# Qwiic_Fuel_Gauge_-_MAX17048.net
KiCad netlist of a schematic drawn in EAGLE
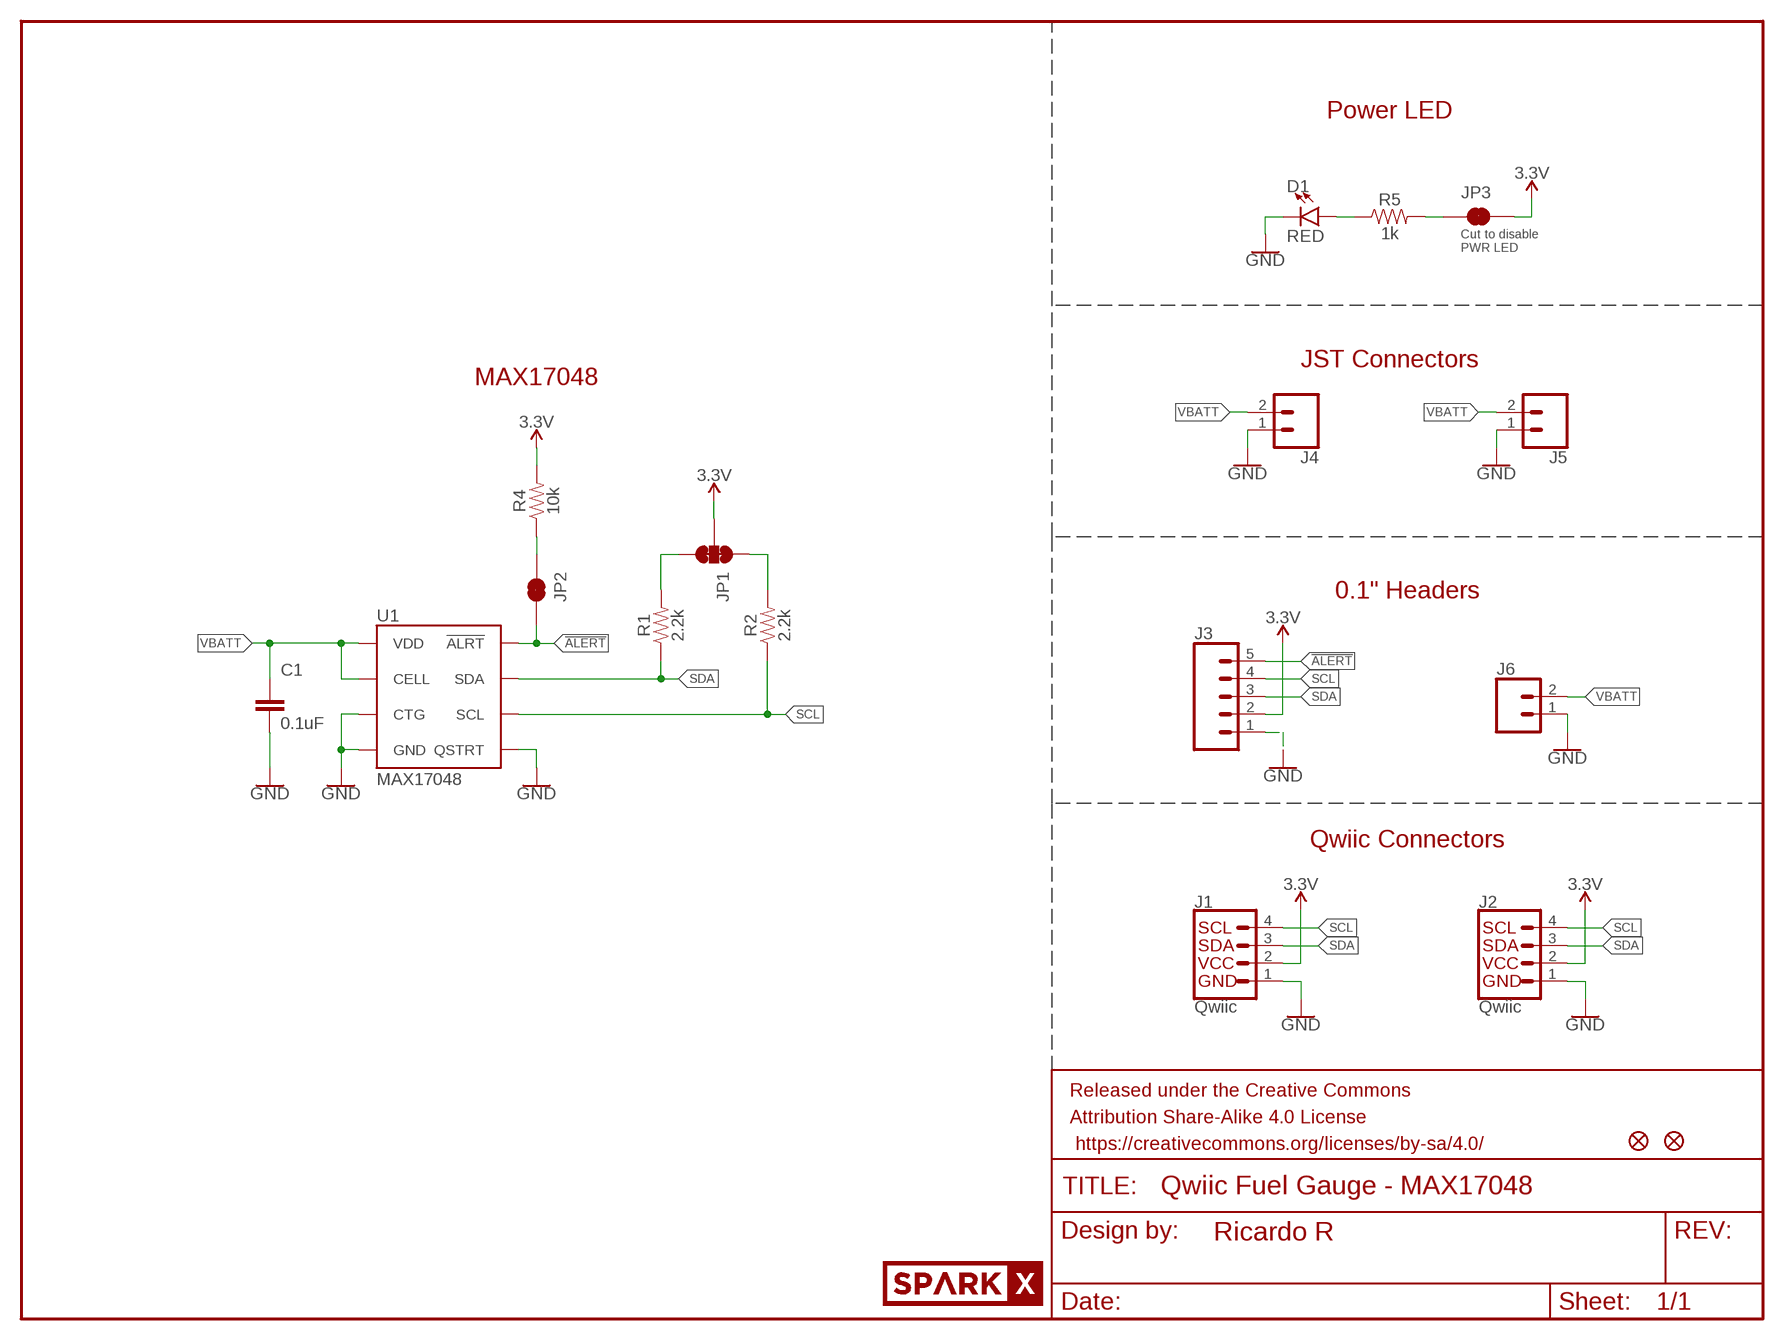
[diagram p0: schematic, sheet 1]

(export (version "E")
  (design (tool "Eeschema 10.0.6"))
  (components
    (comp (ref "C1")
      (value "0.1uF")
      (footprint "eagle-import:0603")
      (libsource (lib "eagle-import") (part "0.1UF-0603-25V-(+80/-20%)"))
    )
    (comp (ref "D1")
      (value "RED")
      (footprint "eagle-import:LED-0603")
      (libsource (lib "eagle-import") (part "LED-RED0603"))
    )
    (comp (ref "FD1")
      (value "FIDUCIAL1X2")
      (footprint "eagle-import:FIDUCIAL-1X2")
      (libsource (lib "eagle-import") (part "FIDUCIAL1X2"))
    )
    (comp (ref "FD2")
      (value "FIDUCIAL1X2")
      (footprint "eagle-import:FIDUCIAL-1X2")
      (libsource (lib "eagle-import") (part "FIDUCIAL1X2"))
    )
    (comp (ref "FRAME1")
      (value "FRAME-LETTERNO_PACKAGE")
      (footprint "eagle-import:DUMMY")
      (fields (field (name "DESIGNER") "Ricardo R") (field (name "DESIGNER_1") "Ricardo R"))
      (libsource (lib "eagle-import") (part "FRAME-LETTERNO_PACKAGE"))
    )
    (comp (ref "J1")
      (value "Qwiic")
      (footprint "eagle-import:JST04_1MM_RA")
      (libsource (lib "eagle-import") (part "QWIIC_CONNECTORJS-1MM"))
    )
    (comp (ref "J2")
      (value "Qwiic")
      (footprint "eagle-import:JST04_1MM_RA")
      (libsource (lib "eagle-import") (part "QWIIC_CONNECTORJS-1MM"))
    )
    (comp (ref "J3")
      (value "CONN_05NO_SILK")
      (footprint "eagle-import:1X05_NO_SILK")
      (libsource (lib "eagle-import") (part "CONN_05NO_SILK"))
    )
    (comp (ref "J4")
      (value "CONN_02-JST-2MM-SMT")
      (footprint "eagle-import:JST-2-SMD")
      (libsource (lib "eagle-import") (part "CONN_02-JST-2MM-SMT"))
    )
    (comp (ref "J5")
      (value "CONN_02-JST-2MM-SMT")
      (footprint "eagle-import:JST-2-SMD")
      (libsource (lib "eagle-import") (part "CONN_02-JST-2MM-SMT"))
    )
    (comp (ref "J6")
      (value "CONN_021X02_NO_SILK")
      (footprint "eagle-import:1X02_NO_SILK")
      (libsource (lib "eagle-import") (part "CONN_021X02_NO_SILK"))
    )
    (comp (ref "JP1")
      (value "JUMPER-SMT_3_2-NC_TRACE_SILK")
      (footprint "eagle-import:SMT-JUMPER_3_2-NC_TRACE_SILK")
      (libsource (lib "eagle-import") (part "JUMPER-SMT_3_2-NC_TRACE_SILK"))
    )
    (comp (ref "JP2")
      (value "JUMPER-SMT_2_NC_TRACE_SILK")
      (footprint "eagle-import:SMT-JUMPER_2_NC_TRACE_SILK")
      (libsource (lib "eagle-import") (part "JUMPER-SMT_2_NC_TRACE_SILK"))
    )
    (comp (ref "JP3")
      (value "JUMPER-SMT_2_NC_TRACE_SILK")
      (footprint "eagle-import:SMT-JUMPER_2_NC_TRACE_SILK")
      (libsource (lib "eagle-import") (part "JUMPER-SMT_2_NC_TRACE_SILK"))
    )
    (comp (ref "R1")
      (value "2.2k")
      (footprint "eagle-import:0603")
      (libsource (lib "eagle-import") (part "2.2KOHM-0603-1/10W-1%"))
    )
    (comp (ref "R2")
      (value "2.2k")
      (footprint "eagle-import:0603")
      (libsource (lib "eagle-import") (part "2.2KOHM-0603-1/10W-1%"))
    )
    (comp (ref "R4")
      (value "10k")
      (footprint "eagle-import:0603")
      (libsource (lib "eagle-import") (part "10KOHM-0603-1/10W-1%"))
    )
    (comp (ref "R5")
      (value "1k")
      (footprint "eagle-import:0603")
      (libsource (lib "eagle-import") (part "1KOHM-0603-1/10W-1%"))
    )
    (comp (ref "U$30")
      (value "SPARKX-LOGO4")
      (footprint "eagle-import:SPARKX-MEDIUM")
      (libsource (lib "eagle-import") (part "SPARKX-LOGO4"))
    )
    (comp (ref "U1")
      (value "MAX17048")
      (footprint "eagle-import:DFN-8")
      (libsource (lib "eagle-import") (part "MAX17048DFN8"))
    )
  )
  (nets
    (net (code "1") (name "/~{ALERT}") (class "Default")
      (node (ref "J3") (pin "5") (pinfunction "5_5") (pintype "passive"))
      (node (ref "JP2") (pin "2") (pinfunction "2_2") (pintype "passive"))
      (node (ref "U1") (pin "5") (pinfunction "~{ALRT}_5") (pintype "bidirectional"))
    )
    (net (code "2") (name "3.3V") (class "Default")
      (node (ref "J1") (pin "2") (pinfunction "2_2") (pintype "power_in"))
      (node (ref "J2") (pin "2") (pinfunction "2_2") (pintype "power_in"))
      (node (ref "J3") (pin "2") (pinfunction "2_2") (pintype "passive"))
      (node (ref "JP1") (pin "2") (pinfunction "2_2") (pintype "passive"))
      (node (ref "JP3") (pin "2") (pinfunction "2_2") (pintype "passive"))
      (node (ref "R4") (pin "2") (pinfunction "2_2") (pintype "passive"))
    )
    (net (code "3") (name "GND") (class "Default")
      (node (ref "C1") (pin "2") (pinfunction "2_2") (pintype "passive"))
      (node (ref "D1") (pin "C") (pinfunction "C_C") (pintype "passive"))
      (node (ref "J1") (pin "1") (pinfunction "1_1") (pintype "power_in"))
      (node (ref "J2") (pin "1") (pinfunction "1_1") (pintype "power_in"))
      (node (ref "J3") (pin "1") (pinfunction "1_1") (pintype "passive"))
      (node (ref "J4") (pin "1") (pinfunction "2_1") (pintype "passive"))
      (node (ref "J5") (pin "1") (pinfunction "2_1") (pintype "passive"))
      (node (ref "J6") (pin "1") (pinfunction "1_1") (pintype "passive"))
      (node (ref "U1") (pin "1") (pinfunction "CTG_1") (pintype "input"))
      (node (ref "U1") (pin "4") (pinfunction "GND_4") (pintype "bidirectional"))
      (node (ref "U1") (pin "6") (pinfunction "QSTRT_6") (pintype "bidirectional"))
      (node (ref "U1") (pin "9") (pinfunction "GND_9") (pintype "bidirectional"))
    )
    (net (code "4") (name "Net-(D1-PadA)") (class "Default")
      (node (ref "D1") (pin "A") (pinfunction "A_A") (pintype "passive"))
      (node (ref "R5") (pin "1") (pinfunction "1_1") (pintype "passive"))
    )
    (net (code "5") (name "Net-(JP1-Pad1)") (class "Default")
      (node (ref "JP1") (pin "1") (pinfunction "1_1") (pintype "passive"))
      (node (ref "R2") (pin "2") (pinfunction "2_2") (pintype "passive"))
    )
    (net (code "6") (name "Net-(JP1-Pad3)") (class "Default")
      (node (ref "JP1") (pin "3") (pinfunction "3_3") (pintype "passive"))
      (node (ref "R1") (pin "2") (pinfunction "2_2") (pintype "passive"))
    )
    (net (code "7") (name "Net-(JP2-Pad1)") (class "Default")
      (node (ref "JP2") (pin "1") (pinfunction "1_1") (pintype "passive"))
      (node (ref "R4") (pin "1") (pinfunction "1_1") (pintype "passive"))
    )
    (net (code "8") (name "Net-(JP3-Pad1)") (class "Default")
      (node (ref "JP3") (pin "1") (pinfunction "1_1") (pintype "passive"))
      (node (ref "R5") (pin "2") (pinfunction "2_2") (pintype "passive"))
    )
    (net (code "9") (name "SCL") (class "Default")
      (node (ref "J1") (pin "4") (pinfunction "4_4") (pintype "passive"))
      (node (ref "J2") (pin "4") (pinfunction "4_4") (pintype "passive"))
      (node (ref "J3") (pin "4") (pinfunction "4_4") (pintype "passive"))
      (node (ref "R2") (pin "1") (pinfunction "1_1") (pintype "passive"))
      (node (ref "U1") (pin "7") (pinfunction "SCL_7") (pintype "output"))
    )
    (net (code "10") (name "SDA") (class "Default")
      (node (ref "J1") (pin "3") (pinfunction "3_3") (pintype "passive"))
      (node (ref "J2") (pin "3") (pinfunction "3_3") (pintype "passive"))
      (node (ref "J3") (pin "3") (pinfunction "3_3") (pintype "passive"))
      (node (ref "R1") (pin "1") (pinfunction "1_1") (pintype "passive"))
      (node (ref "U1") (pin "8") (pinfunction "SDA_8") (pintype "input"))
    )
    (net (code "11") (name "VBATT") (class "Default")
      (node (ref "C1") (pin "1") (pinfunction "1_1") (pintype "passive"))
      (node (ref "J4") (pin "2") (pinfunction "1_2") (pintype "passive"))
      (node (ref "J5") (pin "2") (pinfunction "1_2") (pintype "passive"))
      (node (ref "J6") (pin "2") (pinfunction "2_2") (pintype "passive"))
      (node (ref "U1") (pin "2") (pinfunction "CELL_2") (pintype "input"))
      (node (ref "U1") (pin "3") (pinfunction "VDD_3") (pintype "bidirectional"))
    )
  )
)
